# Bus_Capacitors.net
KiCad netlist of a schematic drawn in Altium Designer
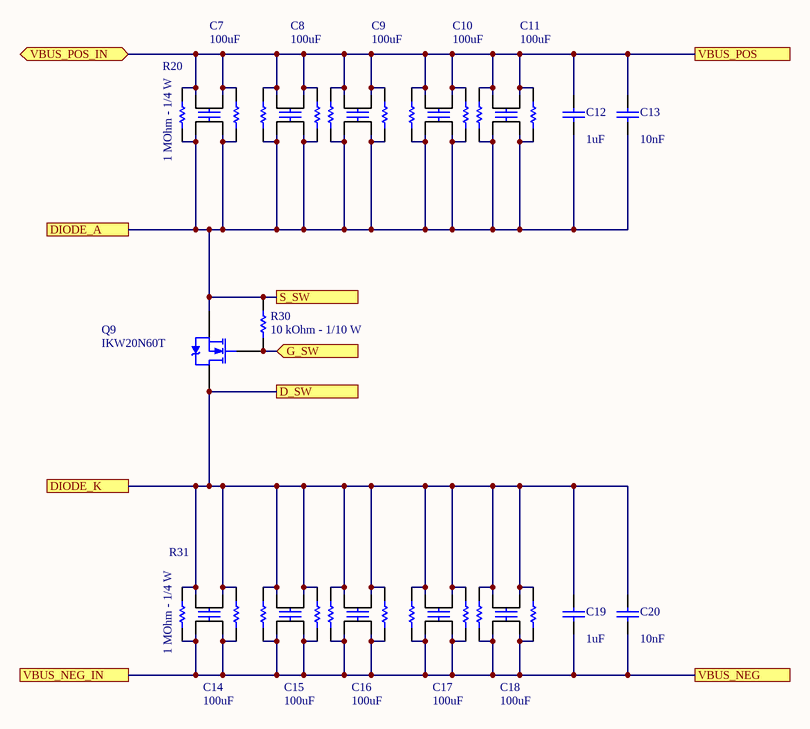
[diagram p0: Bus_Capacitors.SchDoc]

(export (version "E")
  (design (tool "Eeschema 10.0.6"))
  (components
    (comp (ref "C7")
      (value "100uF")
      (footprint "MKP DC link - High density series")
      (description "MKP DC link - High density series - 100uF 450V")
      (fields (field (name "Comment") "EPCOS B32778G4107") (field (name "PUBLISHER") "Altium Limited"))
      (libsource (lib "Capacitor") (part "EPCOS B32778G4107"))
    )
    (comp (ref "C8")
      (value "100uF")
      (footprint "MKP DC link - High density series")
      (description "MKP DC link - High density series - 100uF 450V")
      (fields (field (name "Comment") "EPCOS B32778G4107") (field (name "PUBLISHER") "Altium Limited"))
      (libsource (lib "Capacitor") (part "EPCOS B32778G4107"))
    )
    (comp (ref "C9")
      (value "100uF")
      (footprint "MKP DC link - High density series")
      (description "MKP DC link - High density series - 100uF 450V")
      (fields (field (name "Comment") "EPCOS B32778G4107") (field (name "PUBLISHER") "Altium Limited"))
      (libsource (lib "Capacitor") (part "EPCOS B32778G4107"))
    )
    (comp (ref "C10")
      (value "100uF")
      (footprint "MKP DC link - High density series")
      (description "MKP DC link - High density series - 100uF 450V")
      (fields (field (name "Comment") "EPCOS B32778G4107") (field (name "PUBLISHER") "Altium Limited"))
      (libsource (lib "Capacitor") (part "EPCOS B32778G4107"))
    )
    (comp (ref "C11")
      (value "100uF")
      (footprint "MKP DC link - High density series")
      (description "MKP DC link - High density series - 100uF 450V")
      (fields (field (name "Comment") "EPCOS B32778G4107") (field (name "PUBLISHER") "Altium Limited"))
      (libsource (lib "Capacitor") (part "EPCOS B32778G4107"))
    )
    (comp (ref "C12")
      (value "1uF")
      (footprint "MKP PITCH:27.5mm SIZE:13.5mmx31.5mm")
      (description "MKP High pulse (wound) 1uF 630Vdc")
      (fields (field (name "Comment") "EPCOS B32654A6105") (field (name "PUBLISHER") "Altium Limited"))
      (libsource (lib "Capacitor") (part "EPCOS B32654A6105"))
    )
    (comp (ref "C13")
      (value "10nF")
      (footprint "MKP PITCH:15mm SIZE:5mmx18mm")
      (description "MKP High pulse (wound) 10nF 1000Vdc")
      (fields (field (name "Comment") "EPCOS B32652A0103") (field (name "PUBLISHER") "Altium Limited"))
      (libsource (lib "Capacitor") (part "EPCOS B32652A0103"))
    )
    (comp (ref "C14")
      (value "100uF")
      (footprint "MKP DC link - High density series")
      (description "MKP DC link - High density series - 100uF 450V")
      (fields (field (name "Comment") "EPCOS B32778G4107") (field (name "PUBLISHER") "Altium Limited"))
      (libsource (lib "Capacitor") (part "EPCOS B32778G4107"))
    )
    (comp (ref "C15")
      (value "100uF")
      (footprint "MKP DC link - High density series")
      (description "MKP DC link - High density series - 100uF 450V")
      (fields (field (name "Comment") "EPCOS B32778G4107") (field (name "PUBLISHER") "Altium Limited"))
      (libsource (lib "Capacitor") (part "EPCOS B32778G4107"))
    )
    (comp (ref "C16")
      (value "100uF")
      (footprint "MKP DC link - High density series")
      (description "MKP DC link - High density series - 100uF 450V")
      (fields (field (name "Comment") "EPCOS B32778G4107") (field (name "PUBLISHER") "Altium Limited"))
      (libsource (lib "Capacitor") (part "EPCOS B32778G4107"))
    )
    (comp (ref "C17")
      (value "100uF")
      (footprint "MKP DC link - High density series")
      (description "MKP DC link - High density series - 100uF 450V")
      (fields (field (name "Comment") "EPCOS B32778G4107") (field (name "PUBLISHER") "Altium Limited"))
      (libsource (lib "Capacitor") (part "EPCOS B32778G4107"))
    )
    (comp (ref "C18")
      (value "100uF")
      (footprint "MKP DC link - High density series")
      (description "MKP DC link - High density series - 100uF 450V")
      (fields (field (name "Comment") "EPCOS B32778G4107") (field (name "PUBLISHER") "Altium Limited"))
      (libsource (lib "Capacitor") (part "EPCOS B32778G4107"))
    )
    (comp (ref "C19")
      (value "1uF")
      (footprint "MKP PITCH:27.5mm SIZE:13.5mmx31.5mm")
      (description "MKP High pulse (wound) 1uF 630Vdc")
      (fields (field (name "Comment") "EPCOS B32654A6105") (field (name "PUBLISHER") "Altium Limited"))
      (libsource (lib "Capacitor") (part "EPCOS B32654A6105"))
    )
    (comp (ref "C20")
      (value "10nF")
      (footprint "MKP PITCH:15mm SIZE:5mmx18mm")
      (description "MKP High pulse (wound) 10nF 1000Vdc")
      (fields (field (name "Comment") "EPCOS B32652A0103") (field (name "PUBLISHER") "Altium Limited"))
      (libsource (lib "Capacitor") (part "EPCOS B32652A0103"))
    )
    (comp (ref "Q9")
      (value "IKW20N60T")
      (footprint "TO-247 Horiz. Heatsink")
      (description "IGBTs LOW LOSS DuoPack 600V 20A")
      (fields (field (name "PUBLISHER") "Altium Limited"))
      (libsource (lib "MOSFET") (part "IPx65R110CFD"))
    )
    (comp (ref "R20")
      (value "1 MOhm - 1/4 W")
      (footprint "SamacSys:RESC3216X60N")
      (description "Resistor")
      (fields
        (field (name "MANUFACTURER_PART_NUMBER") "THT")
        (field (name "MOUSER PART NUMBER") "71-CRCW1206-220K-E3")
      )
      (libsource (lib "SamacSys") (part "CRCW1206220KFKEA"))
    )
    (comp (ref "R21")
      (value "THT")
      (footprint "SamacSys:RESC3216X60N")
      (description "Resistor")
      (fields (field (name "MOUSER PART NUMBER") "71-CRCW1206-220K-E3"))
      (libsource (lib "SamacSys") (part "CRCW1206220KFKEA"))
    )
    (comp (ref "R22")
      (value "THT")
      (footprint "SamacSys:RESC3216X60N")
      (description "Resistor")
      (fields (field (name "MOUSER PART NUMBER") "71-CRCW1206-220K-E3"))
      (libsource (lib "SamacSys") (part "CRCW1206220KFKEA"))
    )
    (comp (ref "R23")
      (value "THT")
      (footprint "SamacSys:RESC3216X60N")
      (description "Resistor")
      (fields (field (name "MOUSER PART NUMBER") "71-CRCW1206-220K-E3"))
      (libsource (lib "SamacSys") (part "CRCW1206220KFKEA"))
    )
    (comp (ref "R24")
      (value "THT")
      (footprint "SamacSys:RESC3216X60N")
      (description "Resistor")
      (fields (field (name "MOUSER PART NUMBER") "71-CRCW1206-220K-E3"))
      (libsource (lib "SamacSys") (part "CRCW1206220KFKEA"))
    )
    (comp (ref "R25")
      (value "THT")
      (footprint "SamacSys:RESC3216X60N")
      (description "Resistor")
      (fields (field (name "MOUSER PART NUMBER") "71-CRCW1206-220K-E3"))
      (libsource (lib "SamacSys") (part "CRCW1206220KFKEA"))
    )
    (comp (ref "R26")
      (value "THT")
      (footprint "SamacSys:RESC3216X60N")
      (description "Resistor")
      (fields (field (name "MOUSER PART NUMBER") "71-CRCW1206-220K-E3"))
      (libsource (lib "SamacSys") (part "CRCW1206220KFKEA"))
    )
    (comp (ref "R27")
      (value "THT")
      (footprint "SamacSys:RESC3216X60N")
      (description "Resistor")
      (fields (field (name "MOUSER PART NUMBER") "71-CRCW1206-220K-E3"))
      (libsource (lib "SamacSys") (part "CRCW1206220KFKEA"))
    )
    (comp (ref "R28")
      (value "THT")
      (footprint "SamacSys:RESC3216X60N")
      (description "Resistor")
      (fields (field (name "MOUSER PART NUMBER") "71-CRCW1206-220K-E3"))
      (libsource (lib "SamacSys") (part "CRCW1206220KFKEA"))
    )
    (comp (ref "R29")
      (value "THT")
      (footprint "SamacSys:RESC3216X60N")
      (description "Resistor")
      (fields (field (name "MOUSER PART NUMBER") "71-CRCW1206-220K-E3"))
      (libsource (lib "SamacSys") (part "CRCW1206220KFKEA"))
    )
    (comp (ref "R30")
      (value "10 kOhm - 1/10 W")
      (footprint "RESC1608X50N")
      (description "Resistor")
      (fields
        (field (name "MANUFACTURER_PART_NUMBER") "CRCW060310K0FKEA")
        (field (name "MOUSER PART NUMBER") "71-CRCW0603-10K-E3")
      )
      (libsource (lib "SamacSys") (part "CRCW060310K0FKEA"))
    )
    (comp (ref "R31")
      (value "1 MOhm - 1/4 W")
      (footprint "SamacSys:RESC3216X60N")
      (description "Resistor")
      (fields
        (field (name "MANUFACTURER_PART_NUMBER") "THT")
        (field (name "MOUSER PART NUMBER") "71-CRCW1206-220K-E3")
      )
      (libsource (lib "SamacSys") (part "CRCW1206220KFKEA"))
    )
    (comp (ref "R32")
      (value "THT")
      (footprint "SamacSys:RESC3216X60N")
      (description "Resistor")
      (fields (field (name "MOUSER PART NUMBER") "71-CRCW1206-220K-E3"))
      (libsource (lib "SamacSys") (part "CRCW1206220KFKEA"))
    )
    (comp (ref "R33")
      (value "THT")
      (footprint "SamacSys:RESC3216X60N")
      (description "Resistor")
      (fields (field (name "MOUSER PART NUMBER") "71-CRCW1206-220K-E3"))
      (libsource (lib "SamacSys") (part "CRCW1206220KFKEA"))
    )
    (comp (ref "R34")
      (value "THT")
      (footprint "SamacSys:RESC3216X60N")
      (description "Resistor")
      (fields (field (name "MOUSER PART NUMBER") "71-CRCW1206-220K-E3"))
      (libsource (lib "SamacSys") (part "CRCW1206220KFKEA"))
    )
    (comp (ref "R35")
      (value "THT")
      (footprint "SamacSys:RESC3216X60N")
      (description "Resistor")
      (fields (field (name "MOUSER PART NUMBER") "71-CRCW1206-220K-E3"))
      (libsource (lib "SamacSys") (part "CRCW1206220KFKEA"))
    )
    (comp (ref "R36")
      (value "THT")
      (footprint "SamacSys:RESC3216X60N")
      (description "Resistor")
      (fields (field (name "MOUSER PART NUMBER") "71-CRCW1206-220K-E3"))
      (libsource (lib "SamacSys") (part "CRCW1206220KFKEA"))
    )
    (comp (ref "R37")
      (value "THT")
      (footprint "SamacSys:RESC3216X60N")
      (description "Resistor")
      (fields (field (name "MOUSER PART NUMBER") "71-CRCW1206-220K-E3"))
      (libsource (lib "SamacSys") (part "CRCW1206220KFKEA"))
    )
    (comp (ref "R38")
      (value "THT")
      (footprint "SamacSys:RESC3216X60N")
      (description "Resistor")
      (fields (field (name "MOUSER PART NUMBER") "71-CRCW1206-220K-E3"))
      (libsource (lib "SamacSys") (part "CRCW1206220KFKEA"))
    )
    (comp (ref "R39")
      (value "THT")
      (footprint "SamacSys:RESC3216X60N")
      (description "Resistor")
      (fields (field (name "MOUSER PART NUMBER") "71-CRCW1206-220K-E3"))
      (libsource (lib "SamacSys") (part "CRCW1206220KFKEA"))
    )
    (comp (ref "R40")
      (value "THT")
      (footprint "SamacSys:RESC3216X60N")
      (description "Resistor")
      (fields (field (name "MOUSER PART NUMBER") "71-CRCW1206-220K-E3"))
      (libsource (lib "SamacSys") (part "CRCW1206220KFKEA"))
    )
  )
  (nets
    (net (code "1") (name "/DIODE_A") (class "Default")
      (node (ref "C10") (pin "3") (pinfunction "3_3") (pintype "passive"))
      (node (ref "C10") (pin "4") (pinfunction "4_4") (pintype "passive"))
      (node (ref "C11") (pin "3") (pinfunction "3_3") (pintype "passive"))
      (node (ref "C11") (pin "4") (pinfunction "4_4") (pintype "passive"))
      (node (ref "C12") (pin "1") (pinfunction "1_1") (pintype "passive"))
      (node (ref "C13") (pin "2") (pinfunction "2_2") (pintype "passive"))
      (node (ref "C7") (pin "3") (pinfunction "3_3") (pintype "passive"))
      (node (ref "C7") (pin "4") (pinfunction "4_4") (pintype "passive"))
      (node (ref "C8") (pin "3") (pinfunction "3_3") (pintype "passive"))
      (node (ref "C8") (pin "4") (pinfunction "4_4") (pintype "passive"))
      (node (ref "C9") (pin "3") (pinfunction "3_3") (pintype "passive"))
      (node (ref "C9") (pin "4") (pinfunction "4_4") (pintype "passive"))
      (node (ref "Q9") (pin "3") (pinfunction "S_3") (pintype "passive"))
      (node (ref "R20") (pin "1") (pinfunction "1_1") (pintype "passive"))
      (node (ref "R21") (pin "1") (pinfunction "1_1") (pintype "passive"))
      (node (ref "R22") (pin "1") (pinfunction "1_1") (pintype "passive"))
      (node (ref "R23") (pin "1") (pinfunction "1_1") (pintype "passive"))
      (node (ref "R24") (pin "1") (pinfunction "1_1") (pintype "passive"))
      (node (ref "R25") (pin "1") (pinfunction "1_1") (pintype "passive"))
      (node (ref "R26") (pin "1") (pinfunction "1_1") (pintype "passive"))
      (node (ref "R27") (pin "1") (pinfunction "1_1") (pintype "passive"))
      (node (ref "R28") (pin "1") (pinfunction "1_1") (pintype "passive"))
      (node (ref "R29") (pin "1") (pinfunction "1_1") (pintype "passive"))
      (node (ref "R30") (pin "2") (pinfunction "2_2") (pintype "passive"))
    )
    (net (code "2") (name "/DIODE_K") (class "Default")
      (node (ref "C14") (pin "1") (pinfunction "1_1") (pintype "passive"))
      (node (ref "C14") (pin "2") (pinfunction "2_2") (pintype "passive"))
      (node (ref "C15") (pin "1") (pinfunction "1_1") (pintype "passive"))
      (node (ref "C15") (pin "2") (pinfunction "2_2") (pintype "passive"))
      (node (ref "C16") (pin "1") (pinfunction "1_1") (pintype "passive"))
      (node (ref "C16") (pin "2") (pinfunction "2_2") (pintype "passive"))
      (node (ref "C17") (pin "1") (pinfunction "1_1") (pintype "passive"))
      (node (ref "C17") (pin "2") (pinfunction "2_2") (pintype "passive"))
      (node (ref "C18") (pin "1") (pinfunction "1_1") (pintype "passive"))
      (node (ref "C18") (pin "2") (pinfunction "2_2") (pintype "passive"))
      (node (ref "C19") (pin "2") (pinfunction "2_2") (pintype "passive"))
      (node (ref "C20") (pin "2") (pinfunction "2_2") (pintype "passive"))
      (node (ref "Q9") (pin "2") (pinfunction "D_2") (pintype "passive"))
      (node (ref "R31") (pin "2") (pinfunction "2_2") (pintype "passive"))
      (node (ref "R32") (pin "2") (pinfunction "2_2") (pintype "passive"))
      (node (ref "R33") (pin "2") (pinfunction "2_2") (pintype "passive"))
      (node (ref "R34") (pin "2") (pinfunction "2_2") (pintype "passive"))
      (node (ref "R35") (pin "2") (pinfunction "2_2") (pintype "passive"))
      (node (ref "R36") (pin "2") (pinfunction "2_2") (pintype "passive"))
      (node (ref "R37") (pin "2") (pinfunction "2_2") (pintype "passive"))
      (node (ref "R38") (pin "2") (pinfunction "2_2") (pintype "passive"))
      (node (ref "R39") (pin "2") (pinfunction "2_2") (pintype "passive"))
      (node (ref "R40") (pin "2") (pinfunction "2_2") (pintype "passive"))
    )
    (net (code "3") (name "/G_SW") (class "Default")
      (node (ref "Q9") (pin "1") (pinfunction "G_1") (pintype "passive"))
      (node (ref "R30") (pin "1") (pinfunction "1_1") (pintype "passive"))
    )
    (net (code "4") (name "/VBUS_NEG") (class "Default")
      (node (ref "C14") (pin "3") (pinfunction "3_3") (pintype "passive"))
      (node (ref "C14") (pin "4") (pinfunction "4_4") (pintype "passive"))
      (node (ref "C15") (pin "3") (pinfunction "3_3") (pintype "passive"))
      (node (ref "C15") (pin "4") (pinfunction "4_4") (pintype "passive"))
      (node (ref "C16") (pin "3") (pinfunction "3_3") (pintype "passive"))
      (node (ref "C16") (pin "4") (pinfunction "4_4") (pintype "passive"))
      (node (ref "C17") (pin "3") (pinfunction "3_3") (pintype "passive"))
      (node (ref "C17") (pin "4") (pinfunction "4_4") (pintype "passive"))
      (node (ref "C18") (pin "3") (pinfunction "3_3") (pintype "passive"))
      (node (ref "C18") (pin "4") (pinfunction "4_4") (pintype "passive"))
      (node (ref "C19") (pin "1") (pinfunction "1_1") (pintype "passive"))
      (node (ref "C20") (pin "1") (pinfunction "1_1") (pintype "passive"))
      (node (ref "R31") (pin "1") (pinfunction "1_1") (pintype "passive"))
      (node (ref "R32") (pin "1") (pinfunction "1_1") (pintype "passive"))
      (node (ref "R33") (pin "1") (pinfunction "1_1") (pintype "passive"))
      (node (ref "R34") (pin "1") (pinfunction "1_1") (pintype "passive"))
      (node (ref "R35") (pin "1") (pinfunction "1_1") (pintype "passive"))
      (node (ref "R36") (pin "1") (pinfunction "1_1") (pintype "passive"))
      (node (ref "R37") (pin "1") (pinfunction "1_1") (pintype "passive"))
      (node (ref "R38") (pin "1") (pinfunction "1_1") (pintype "passive"))
      (node (ref "R39") (pin "1") (pinfunction "1_1") (pintype "passive"))
      (node (ref "R40") (pin "1") (pinfunction "1_1") (pintype "passive"))
    )
    (net (code "5") (name "/VBUS_POS") (class "Default")
      (node (ref "C10") (pin "1") (pinfunction "1_1") (pintype "passive"))
      (node (ref "C10") (pin "2") (pinfunction "2_2") (pintype "passive"))
      (node (ref "C11") (pin "1") (pinfunction "1_1") (pintype "passive"))
      (node (ref "C11") (pin "2") (pinfunction "2_2") (pintype "passive"))
      (node (ref "C12") (pin "2") (pinfunction "2_2") (pintype "passive"))
      (node (ref "C13") (pin "1") (pinfunction "1_1") (pintype "passive"))
      (node (ref "C7") (pin "1") (pinfunction "1_1") (pintype "passive"))
      (node (ref "C7") (pin "2") (pinfunction "2_2") (pintype "passive"))
      (node (ref "C8") (pin "1") (pinfunction "1_1") (pintype "passive"))
      (node (ref "C8") (pin "2") (pinfunction "2_2") (pintype "passive"))
      (node (ref "C9") (pin "1") (pinfunction "1_1") (pintype "passive"))
      (node (ref "C9") (pin "2") (pinfunction "2_2") (pintype "passive"))
      (node (ref "R20") (pin "2") (pinfunction "2_2") (pintype "passive"))
      (node (ref "R21") (pin "2") (pinfunction "2_2") (pintype "passive"))
      (node (ref "R22") (pin "2") (pinfunction "2_2") (pintype "passive"))
      (node (ref "R23") (pin "2") (pinfunction "2_2") (pintype "passive"))
      (node (ref "R24") (pin "2") (pinfunction "2_2") (pintype "passive"))
      (node (ref "R25") (pin "2") (pinfunction "2_2") (pintype "passive"))
      (node (ref "R26") (pin "2") (pinfunction "2_2") (pintype "passive"))
      (node (ref "R27") (pin "2") (pinfunction "2_2") (pintype "passive"))
      (node (ref "R28") (pin "2") (pinfunction "2_2") (pintype "passive"))
      (node (ref "R29") (pin "2") (pinfunction "2_2") (pintype "passive"))
    )
  )
)
